# 1_0.net
KiCad netlist of a schematic drawn in EAGLE
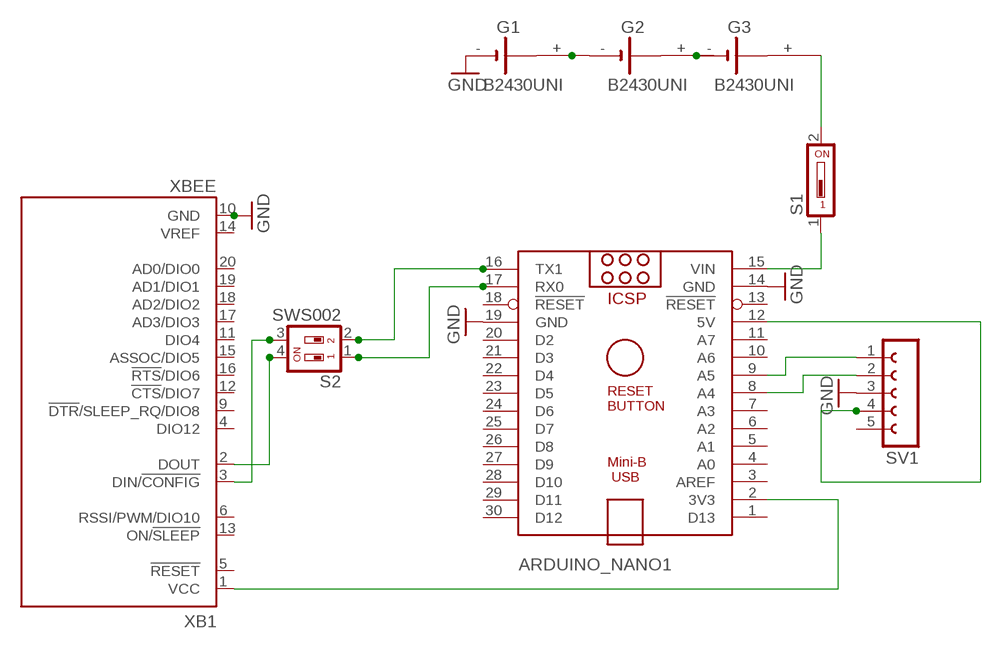
[diagram p0: schematic, sheet 1]

(export (version "E")
  (design (tool "Eeschema 10.0.6"))
  (components
    (comp (ref "ARDUINO_NANO1")
      (value "ARDUINO_NANO")
      (footprint "eagle-import:ARDUINO_NANO")
      (libsource (lib "eagle-import") (part "ARDUINO_NANO"))
    )
    (comp (ref "G1")
      (value "B2430UNI")
      (footprint "eagle-import:B2430UNI")
      (libsource (lib "eagle-import") (part "B2430UNI"))
    )
    (comp (ref "G2")
      (value "B2430UNI")
      (footprint "eagle-import:B2430UNI")
      (libsource (lib "eagle-import") (part "B2430UNI"))
    )
    (comp (ref "G3")
      (value "B2430UNI")
      (footprint "eagle-import:B2430UNI")
      (libsource (lib "eagle-import") (part "B2430UNI"))
    )
    (comp (ref "S1")
      (value "DS01")
      (footprint "eagle-import:DS-01")
      (libsource (lib "eagle-import") (part "DS01"))
    )
    (comp (ref "S2")
      (value "SWS002")
      (footprint "eagle-import:SMS-002")
      (libsource (lib "eagle-import") (part "SWS002"))
    )
    (comp (ref "SV1")
      (value "FE05-1")
      (footprint "eagle-import:FE05-1")
      (libsource (lib "eagle-import") (part "FE05-1"))
    )
    (comp (ref "XB1")
      (value "XBEE")
      (footprint "eagle-import:XBEE")
      (fields (field (name "MPN") "XBP24-Z7UIT-004"))
      (libsource (lib "eagle-import") (part "XBEE"))
    )
  )
  (nets
    (net (code "1") (name "GND") (class "Default")
      (node (ref "ARDUINO_NANO1") (pin "14") (pinfunction "GND_14") (pintype "power_in"))
      (node (ref "ARDUINO_NANO1") (pin "19") (pinfunction "GND_19") (pintype "power_in"))
      (node (ref "G1") (pin "-") (pinfunction "-_-") (pintype "passive"))
      (node (ref "SV1") (pin "3") (pinfunction "3_3") (pintype "passive"))
      (node (ref "XB1") (pin "10") (pinfunction "GND_10") (pintype "power_in"))
    )
    (net (code "2") (name "Net-(ARDUINO_NANO1-3V3)") (class "Default")
      (node (ref "ARDUINO_NANO1") (pin "2") (pinfunction "3V3_2") (pintype "output"))
      (node (ref "XB1") (pin "1") (pinfunction "VCC_1") (pintype "power_in"))
    )
    (net (code "3") (name "Net-(ARDUINO_NANO1-5V)") (class "Default")
      (node (ref "ARDUINO_NANO1") (pin "12") (pinfunction "5V_12") (pintype "power_in"))
      (node (ref "SV1") (pin "4") (pinfunction "4_4") (pintype "passive"))
    )
    (net (code "4") (name "Net-(ARDUINO_NANO1-A4)") (class "Default")
      (node (ref "ARDUINO_NANO1") (pin "8") (pinfunction "A4_8") (pintype "bidirectional"))
      (node (ref "SV1") (pin "2") (pinfunction "2_2") (pintype "passive"))
    )
    (net (code "5") (name "Net-(ARDUINO_NANO1-A5)") (class "Default")
      (node (ref "ARDUINO_NANO1") (pin "9") (pinfunction "A5_9") (pintype "bidirectional"))
      (node (ref "SV1") (pin "1") (pinfunction "1_1") (pintype "passive"))
    )
    (net (code "6") (name "Net-(ARDUINO_NANO1-RX0)") (class "Default")
      (node (ref "ARDUINO_NANO1") (pin "17") (pinfunction "RX0_17") (pintype "bidirectional"))
      (node (ref "S2") (pin "1") (pinfunction "1_1") (pintype "passive"))
    )
    (net (code "7") (name "Net-(ARDUINO_NANO1-TX1)") (class "Default")
      (node (ref "ARDUINO_NANO1") (pin "16") (pinfunction "TX1_16") (pintype "bidirectional"))
      (node (ref "S2") (pin "2") (pinfunction "2_2") (pintype "passive"))
    )
    (net (code "8") (name "Net-(ARDUINO_NANO1-VIN)") (class "Default")
      (node (ref "ARDUINO_NANO1") (pin "15") (pinfunction "VIN_15") (pintype "power_in"))
      (node (ref "S1") (pin "1") (pinfunction "1_1") (pintype "passive"))
    )
    (net (code "9") (name "Net-(G1-Pad+)") (class "Default")
      (node (ref "G1") (pin "+") (pinfunction "+_+") (pintype "passive"))
      (node (ref "G2") (pin "-") (pinfunction "-_-") (pintype "passive"))
    )
    (net (code "10") (name "Net-(G2-+-Pad+@1)") (class "Default")
      (node (ref "G2") (pin "+@1") (pinfunction "+_+@1") (pintype "passive"))
      (node (ref "G3") (pin "-") (pinfunction "-_-") (pintype "passive"))
    )
    (net (code "11") (name "Net-(G2-Pad+)") (class "Default")
      (node (ref "G2") (pin "+") (pinfunction "+_+") (pintype "passive"))
      (node (ref "G3") (pin "-@1") (pinfunction "-_-@1") (pintype "passive"))
    )
    (net (code "12") (name "Net-(G3-Pad+)") (class "Default")
      (node (ref "G3") (pin "+") (pinfunction "+_+") (pintype "passive"))
      (node (ref "S1") (pin "2") (pinfunction "2_2") (pintype "passive"))
    )
    (net (code "13") (name "Net-(XB1-DIN{slash}~{CONFIG})") (class "Default")
      (node (ref "S2") (pin "3") (pinfunction "3_3") (pintype "passive"))
      (node (ref "XB1") (pin "3") (pinfunction "DIN/~{CONFIG}_3") (pintype "input"))
    )
    (net (code "14") (name "Net-(XB1-DOUT)") (class "Default")
      (node (ref "S2") (pin "4") (pinfunction "4_4") (pintype "passive"))
      (node (ref "XB1") (pin "2") (pinfunction "DOUT_2") (pintype "output"))
    )
    (net (code "15") (name "unconnected-(ARDUINO_NANO1-A0-Pad4)") (class "Default")
      (node (ref "ARDUINO_NANO1") (pin "4") (pinfunction "A0_4") (pintype "bidirectional"))
    )
    (net (code "16") (name "unconnected-(ARDUINO_NANO1-A1-Pad5)") (class "Default")
      (node (ref "ARDUINO_NANO1") (pin "5") (pinfunction "A1_5") (pintype "bidirectional"))
    )
    (net (code "17") (name "unconnected-(ARDUINO_NANO1-A2-Pad6)") (class "Default")
      (node (ref "ARDUINO_NANO1") (pin "6") (pinfunction "A2_6") (pintype "bidirectional"))
    )
    (net (code "18") (name "unconnected-(ARDUINO_NANO1-A3-Pad7)") (class "Default")
      (node (ref "ARDUINO_NANO1") (pin "7") (pinfunction "A3_7") (pintype "bidirectional"))
    )
    (net (code "19") (name "unconnected-(ARDUINO_NANO1-A6-Pad10)") (class "Default")
      (node (ref "ARDUINO_NANO1") (pin "10") (pinfunction "A6_10") (pintype "bidirectional"))
    )
    (net (code "20") (name "unconnected-(ARDUINO_NANO1-A7-Pad11)") (class "Default")
      (node (ref "ARDUINO_NANO1") (pin "11") (pinfunction "A7_11") (pintype "bidirectional"))
    )
    (net (code "21") (name "unconnected-(ARDUINO_NANO1-AREF-Pad3)") (class "Default")
      (node (ref "ARDUINO_NANO1") (pin "3") (pinfunction "AREF_3") (pintype "input"))
    )
    (net (code "22") (name "unconnected-(ARDUINO_NANO1-D2-Pad20)") (class "Default")
      (node (ref "ARDUINO_NANO1") (pin "20") (pinfunction "D2_20") (pintype "bidirectional"))
    )
    (net (code "23") (name "unconnected-(ARDUINO_NANO1-D3-Pad21)") (class "Default")
      (node (ref "ARDUINO_NANO1") (pin "21") (pinfunction "D3_21") (pintype "bidirectional"))
    )
    (net (code "24") (name "unconnected-(ARDUINO_NANO1-D4-Pad22)") (class "Default")
      (node (ref "ARDUINO_NANO1") (pin "22") (pinfunction "D4_22") (pintype "bidirectional"))
    )
    (net (code "25") (name "unconnected-(ARDUINO_NANO1-D5-Pad23)") (class "Default")
      (node (ref "ARDUINO_NANO1") (pin "23") (pinfunction "D5_23") (pintype "bidirectional"))
    )
    (net (code "26") (name "unconnected-(ARDUINO_NANO1-D6-Pad24)") (class "Default")
      (node (ref "ARDUINO_NANO1") (pin "24") (pinfunction "D6_24") (pintype "bidirectional"))
    )
    (net (code "27") (name "unconnected-(ARDUINO_NANO1-D7-Pad25)") (class "Default")
      (node (ref "ARDUINO_NANO1") (pin "25") (pinfunction "D7_25") (pintype "bidirectional"))
    )
    (net (code "28") (name "unconnected-(ARDUINO_NANO1-D8-Pad26)") (class "Default")
      (node (ref "ARDUINO_NANO1") (pin "26") (pinfunction "D8_26") (pintype "bidirectional"))
    )
    (net (code "29") (name "unconnected-(ARDUINO_NANO1-D9-Pad27)") (class "Default")
      (node (ref "ARDUINO_NANO1") (pin "27") (pinfunction "D9_27") (pintype "bidirectional"))
    )
    (net (code "30") (name "unconnected-(ARDUINO_NANO1-D10-Pad28)") (class "Default")
      (node (ref "ARDUINO_NANO1") (pin "28") (pinfunction "D10_28") (pintype "bidirectional"))
    )
    (net (code "31") (name "unconnected-(ARDUINO_NANO1-D11-Pad29)") (class "Default")
      (node (ref "ARDUINO_NANO1") (pin "29") (pinfunction "D11_29") (pintype "bidirectional"))
    )
    (net (code "32") (name "unconnected-(ARDUINO_NANO1-D12-Pad30)") (class "Default")
      (node (ref "ARDUINO_NANO1") (pin "30") (pinfunction "D12_30") (pintype "bidirectional"))
    )
    (net (code "33") (name "unconnected-(ARDUINO_NANO1-D13-Pad1)") (class "Default")
      (node (ref "ARDUINO_NANO1") (pin "1") (pinfunction "D13_1") (pintype "bidirectional"))
    )
    (net (code "34") (name "unconnected-(ARDUINO_NANO1-~{RESET}-Pad13)") (class "Default")
      (node (ref "ARDUINO_NANO1") (pin "13") (pinfunction "~{RESET}_13") (pintype "input"))
    )
    (net (code "35") (name "unconnected-(ARDUINO_NANO1-~{RESET}-Pad18)") (class "Default")
      (node (ref "ARDUINO_NANO1") (pin "18") (pinfunction "~{RESET}_18") (pintype "input"))
    )
    (net (code "36") (name "unconnected-(G1-+-Pad+@1)") (class "Default")
      (node (ref "G1") (pin "+@1") (pinfunction "+_+@1") (pintype "passive"))
    )
    (net (code "37") (name "unconnected-(G1-+-Pad+@2)") (class "Default")
      (node (ref "G1") (pin "+@2") (pinfunction "+_+@2") (pintype "passive"))
    )
    (net (code "38") (name "unconnected-(G1-+-Pad+@3)") (class "Default")
      (node (ref "G1") (pin "+@3") (pinfunction "+_+@3") (pintype "passive"))
    )
    (net (code "39") (name "unconnected-(G1-+-Pad+@4)") (class "Default")
      (node (ref "G1") (pin "+@4") (pinfunction "+_+@4") (pintype "passive"))
    )
    (net (code "40") (name "unconnected-(G1---Pad-@1)") (class "Default")
      (node (ref "G1") (pin "-@1") (pinfunction "-_-@1") (pintype "passive"))
    )
    (net (code "41") (name "unconnected-(G2-+-Pad+@2)") (class "Default")
      (node (ref "G2") (pin "+@2") (pinfunction "+_+@2") (pintype "passive"))
    )
    (net (code "42") (name "unconnected-(G2-+-Pad+@3)") (class "Default")
      (node (ref "G2") (pin "+@3") (pinfunction "+_+@3") (pintype "passive"))
    )
    (net (code "43") (name "unconnected-(G2-+-Pad+@4)") (class "Default")
      (node (ref "G2") (pin "+@4") (pinfunction "+_+@4") (pintype "passive"))
    )
    (net (code "44") (name "unconnected-(G2---Pad-@1)") (class "Default")
      (node (ref "G2") (pin "-@1") (pinfunction "-_-@1") (pintype "passive"))
    )
    (net (code "45") (name "unconnected-(G3-+-Pad+@1)") (class "Default")
      (node (ref "G3") (pin "+@1") (pinfunction "+_+@1") (pintype "passive"))
    )
    (net (code "46") (name "unconnected-(G3-+-Pad+@2)") (class "Default")
      (node (ref "G3") (pin "+@2") (pinfunction "+_+@2") (pintype "passive"))
    )
    (net (code "47") (name "unconnected-(G3-+-Pad+@3)") (class "Default")
      (node (ref "G3") (pin "+@3") (pinfunction "+_+@3") (pintype "passive"))
    )
    (net (code "48") (name "unconnected-(G3-+-Pad+@4)") (class "Default")
      (node (ref "G3") (pin "+@4") (pinfunction "+_+@4") (pintype "passive"))
    )
    (net (code "49") (name "unconnected-(SV1-Pad5)") (class "Default")
      (node (ref "SV1") (pin "5") (pinfunction "5_5") (pintype "passive"))
    )
    (net (code "50") (name "unconnected-(XB1-AD0{slash}DIO0-Pad20)") (class "Default")
      (node (ref "XB1") (pin "20") (pinfunction "AD0/DIO0_20") (pintype "bidirectional"))
    )
    (net (code "51") (name "unconnected-(XB1-AD1{slash}DIO1-Pad19)") (class "Default")
      (node (ref "XB1") (pin "19") (pinfunction "AD1/DIO1_19") (pintype "bidirectional"))
    )
    (net (code "52") (name "unconnected-(XB1-AD2{slash}DIO2-Pad18)") (class "Default")
      (node (ref "XB1") (pin "18") (pinfunction "AD2/DIO2_18") (pintype "bidirectional"))
    )
    (net (code "53") (name "unconnected-(XB1-AD3{slash}DIO3-Pad17)") (class "Default")
      (node (ref "XB1") (pin "17") (pinfunction "AD3/DIO3_17") (pintype "bidirectional"))
    )
    (net (code "54") (name "unconnected-(XB1-ASSOC{slash}DIO5-Pad15)") (class "Default")
      (node (ref "XB1") (pin "15") (pinfunction "ASSOC/DIO5_15") (pintype "bidirectional"))
    )
    (net (code "55") (name "unconnected-(XB1-DIO4-Pad11)") (class "Default")
      (node (ref "XB1") (pin "11") (pinfunction "DIO4_11") (pintype "bidirectional"))
    )
    (net (code "56") (name "unconnected-(XB1-DIO12-Pad4)") (class "Default")
      (node (ref "XB1") (pin "4") (pinfunction "DIO12_4") (pintype "bidirectional"))
    )
    (net (code "57") (name "unconnected-(XB1-ON{slash}~{SLEEP}-Pad13)") (class "Default")
      (node (ref "XB1") (pin "13") (pinfunction "ON/~{SLEEP}_13") (pintype "output"))
    )
    (net (code "58") (name "unconnected-(XB1-RSSI{slash}PWM{slash}DIO10-Pad6)") (class "Default")
      (node (ref "XB1") (pin "6") (pinfunction "RSSI/PWM/DIO10_6") (pintype "output"))
    )
    (net (code "59") (name "unconnected-(XB1-VREF-Pad14)") (class "Default")
      (node (ref "XB1") (pin "14") (pinfunction "VREF_14") (pintype "input"))
    )
    (net (code "60") (name "unconnected-(XB1-~{CTS}{slash}DIO7-Pad12)") (class "Default")
      (node (ref "XB1") (pin "12") (pinfunction "~{CTS}/DIO7_12") (pintype "bidirectional"))
    )
    (net (code "61") (name "unconnected-(XB1-~{DTR}{slash}SLEEP_RQ{slash}DIO8-Pad9)") (class "Default")
      (node (ref "XB1") (pin "9") (pinfunction "~{DTR}/SLEEP_RQ/DIO8_9") (pintype "bidirectional"))
    )
    (net (code "62") (name "unconnected-(XB1-~{RESET}-Pad5)") (class "Default")
      (node (ref "XB1") (pin "5") (pinfunction "~{RESET}_5") (pintype "input"))
    )
    (net (code "63") (name "unconnected-(XB1-~{RTS}{slash}DIO6-Pad16)") (class "Default")
      (node (ref "XB1") (pin "16") (pinfunction "~{RTS}/DIO6_16") (pintype "bidirectional"))
    )
  )
)
